# IF_Connectors.net
KiCad netlist of a schematic drawn in Altium Designer
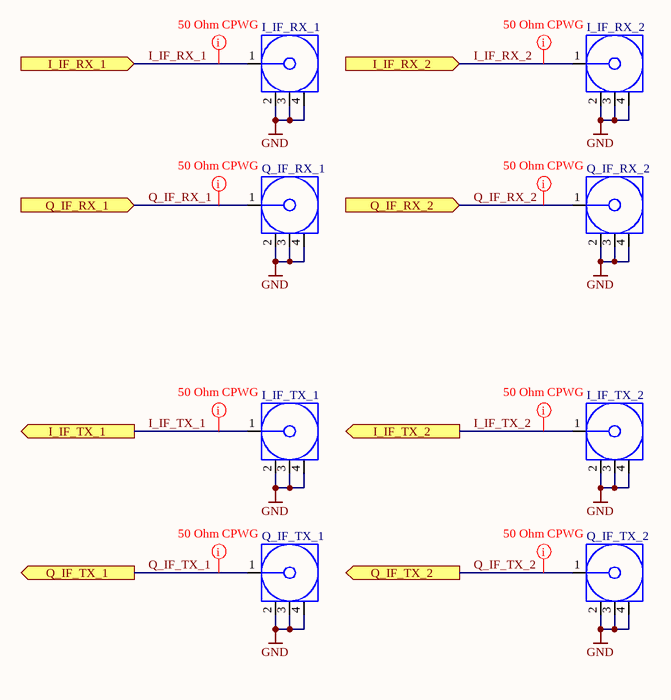
[diagram p0: IF_Connectors.SchDoc]

(export (version "E")
  (design (tool "Eeschema 10.0.6"))
  (components
    (comp (ref "I_IF_RX_1")
      (value "60312862112552")
      (footprint "60312862112552")
      (description "WR-SMA Connector, PCB Solderless, DC~18GHz, 50Ohm")
      (fields (field (name "MANUFACTURER") "Würth"))
      (libsource (lib "database_library") (part "60312862112552"))
    )
    (comp (ref "I_IF_RX_2")
      (value "60312862112552")
      (footprint "60312862112552")
      (description "WR-SMA Connector, PCB Solderless, DC~18GHz, 50Ohm")
      (fields (field (name "MANUFACTURER") "Würth"))
      (libsource (lib "database_library") (part "60312862112552"))
    )
    (comp (ref "I_IF_TX_1")
      (value "60312862112552")
      (footprint "60312862112552")
      (description "WR-SMA Connector, PCB Solderless, DC~18GHz, 50Ohm")
      (fields (field (name "MANUFACTURER") "Würth"))
      (libsource (lib "database_library") (part "60312862112552"))
    )
    (comp (ref "I_IF_TX_2")
      (value "60312862112552")
      (footprint "60312862112552")
      (description "WR-SMA Connector, PCB Solderless, DC~18GHz, 50Ohm")
      (fields (field (name "MANUFACTURER") "Würth"))
      (libsource (lib "database_library") (part "60312862112552"))
    )
    (comp (ref "Q_IF_RX_1")
      (value "60312862112552")
      (footprint "60312862112552")
      (description "WR-SMA Connector, PCB Solderless, DC~18GHz, 50Ohm")
      (fields (field (name "MANUFACTURER") "Würth"))
      (libsource (lib "database_library") (part "60312862112552"))
    )
    (comp (ref "Q_IF_RX_2")
      (value "60312862112552")
      (footprint "60312862112552")
      (description "WR-SMA Connector, PCB Solderless, DC~18GHz, 50Ohm")
      (fields (field (name "MANUFACTURER") "Würth"))
      (libsource (lib "database_library") (part "60312862112552"))
    )
    (comp (ref "Q_IF_TX_1")
      (value "60312862112552")
      (footprint "60312862112552")
      (description "WR-SMA Connector, PCB Solderless, DC~18GHz, 50Ohm")
      (fields (field (name "MANUFACTURER") "Würth"))
      (libsource (lib "database_library") (part "60312862112552"))
    )
    (comp (ref "Q_IF_TX_2")
      (value "60312862112552")
      (footprint "60312862112552")
      (description "WR-SMA Connector, PCB Solderless, DC~18GHz, 50Ohm")
      (fields (field (name "MANUFACTURER") "Würth"))
      (libsource (lib "database_library") (part "60312862112552"))
    )
  )
  (nets
    (net (code "1") (name "/I_IF_RX_1") (class "Default")
      (node (ref "I_IF_RX_1") (pin "1") (pinfunction "Signal_1") (pintype "passive"))
    )
    (net (code "2") (name "/I_IF_RX_2") (class "Default")
      (node (ref "I_IF_RX_2") (pin "1") (pinfunction "Signal_1") (pintype "passive"))
    )
    (net (code "3") (name "/I_IF_TX_1") (class "Default")
      (node (ref "I_IF_TX_1") (pin "1") (pinfunction "Signal_1") (pintype "passive"))
    )
    (net (code "4") (name "/I_IF_TX_2") (class "Default")
      (node (ref "I_IF_TX_2") (pin "1") (pinfunction "Signal_1") (pintype "passive"))
    )
    (net (code "5") (name "/Q_IF_RX_1") (class "Default")
      (node (ref "Q_IF_RX_1") (pin "1") (pinfunction "Signal_1") (pintype "passive"))
    )
    (net (code "6") (name "/Q_IF_RX_2") (class "Default")
      (node (ref "Q_IF_RX_2") (pin "1") (pinfunction "Signal_1") (pintype "passive"))
    )
    (net (code "7") (name "/Q_IF_TX_1") (class "Default")
      (node (ref "Q_IF_TX_1") (pin "1") (pinfunction "Signal_1") (pintype "passive"))
    )
    (net (code "8") (name "/Q_IF_TX_2") (class "Default")
      (node (ref "Q_IF_TX_2") (pin "1") (pinfunction "Signal_1") (pintype "passive"))
    )
    (net (code "9") (name "GND") (class "Default")
      (node (ref "I_IF_RX_1") (pin "2") (pinfunction "GND_2") (pintype "passive"))
      (node (ref "I_IF_RX_1") (pin "3") (pinfunction "GND_3") (pintype "passive"))
      (node (ref "I_IF_RX_1") (pin "4") (pinfunction "GND_4") (pintype "passive"))
      (node (ref "I_IF_RX_2") (pin "2") (pinfunction "GND_2") (pintype "passive"))
      (node (ref "I_IF_RX_2") (pin "3") (pinfunction "GND_3") (pintype "passive"))
      (node (ref "I_IF_RX_2") (pin "4") (pinfunction "GND_4") (pintype "passive"))
      (node (ref "I_IF_TX_1") (pin "2") (pinfunction "GND_2") (pintype "passive"))
      (node (ref "I_IF_TX_1") (pin "3") (pinfunction "GND_3") (pintype "passive"))
      (node (ref "I_IF_TX_1") (pin "4") (pinfunction "GND_4") (pintype "passive"))
      (node (ref "I_IF_TX_2") (pin "2") (pinfunction "GND_2") (pintype "passive"))
      (node (ref "I_IF_TX_2") (pin "3") (pinfunction "GND_3") (pintype "passive"))
      (node (ref "I_IF_TX_2") (pin "4") (pinfunction "GND_4") (pintype "passive"))
      (node (ref "Q_IF_RX_1") (pin "2") (pinfunction "GND_2") (pintype "passive"))
      (node (ref "Q_IF_RX_1") (pin "3") (pinfunction "GND_3") (pintype "passive"))
      (node (ref "Q_IF_RX_1") (pin "4") (pinfunction "GND_4") (pintype "passive"))
      (node (ref "Q_IF_RX_2") (pin "2") (pinfunction "GND_2") (pintype "passive"))
      (node (ref "Q_IF_RX_2") (pin "3") (pinfunction "GND_3") (pintype "passive"))
      (node (ref "Q_IF_RX_2") (pin "4") (pinfunction "GND_4") (pintype "passive"))
      (node (ref "Q_IF_TX_1") (pin "2") (pinfunction "GND_2") (pintype "passive"))
      (node (ref "Q_IF_TX_1") (pin "3") (pinfunction "GND_3") (pintype "passive"))
      (node (ref "Q_IF_TX_1") (pin "4") (pinfunction "GND_4") (pintype "passive"))
      (node (ref "Q_IF_TX_2") (pin "2") (pinfunction "GND_2") (pintype "passive"))
      (node (ref "Q_IF_TX_2") (pin "3") (pinfunction "GND_3") (pintype "passive"))
      (node (ref "Q_IF_TX_2") (pin "4") (pinfunction "GND_4") (pintype "passive"))
    )
  )
)
